# Mikrolysreklamen17.net
KiCad netlist of a schematic drawn in Altium Designer
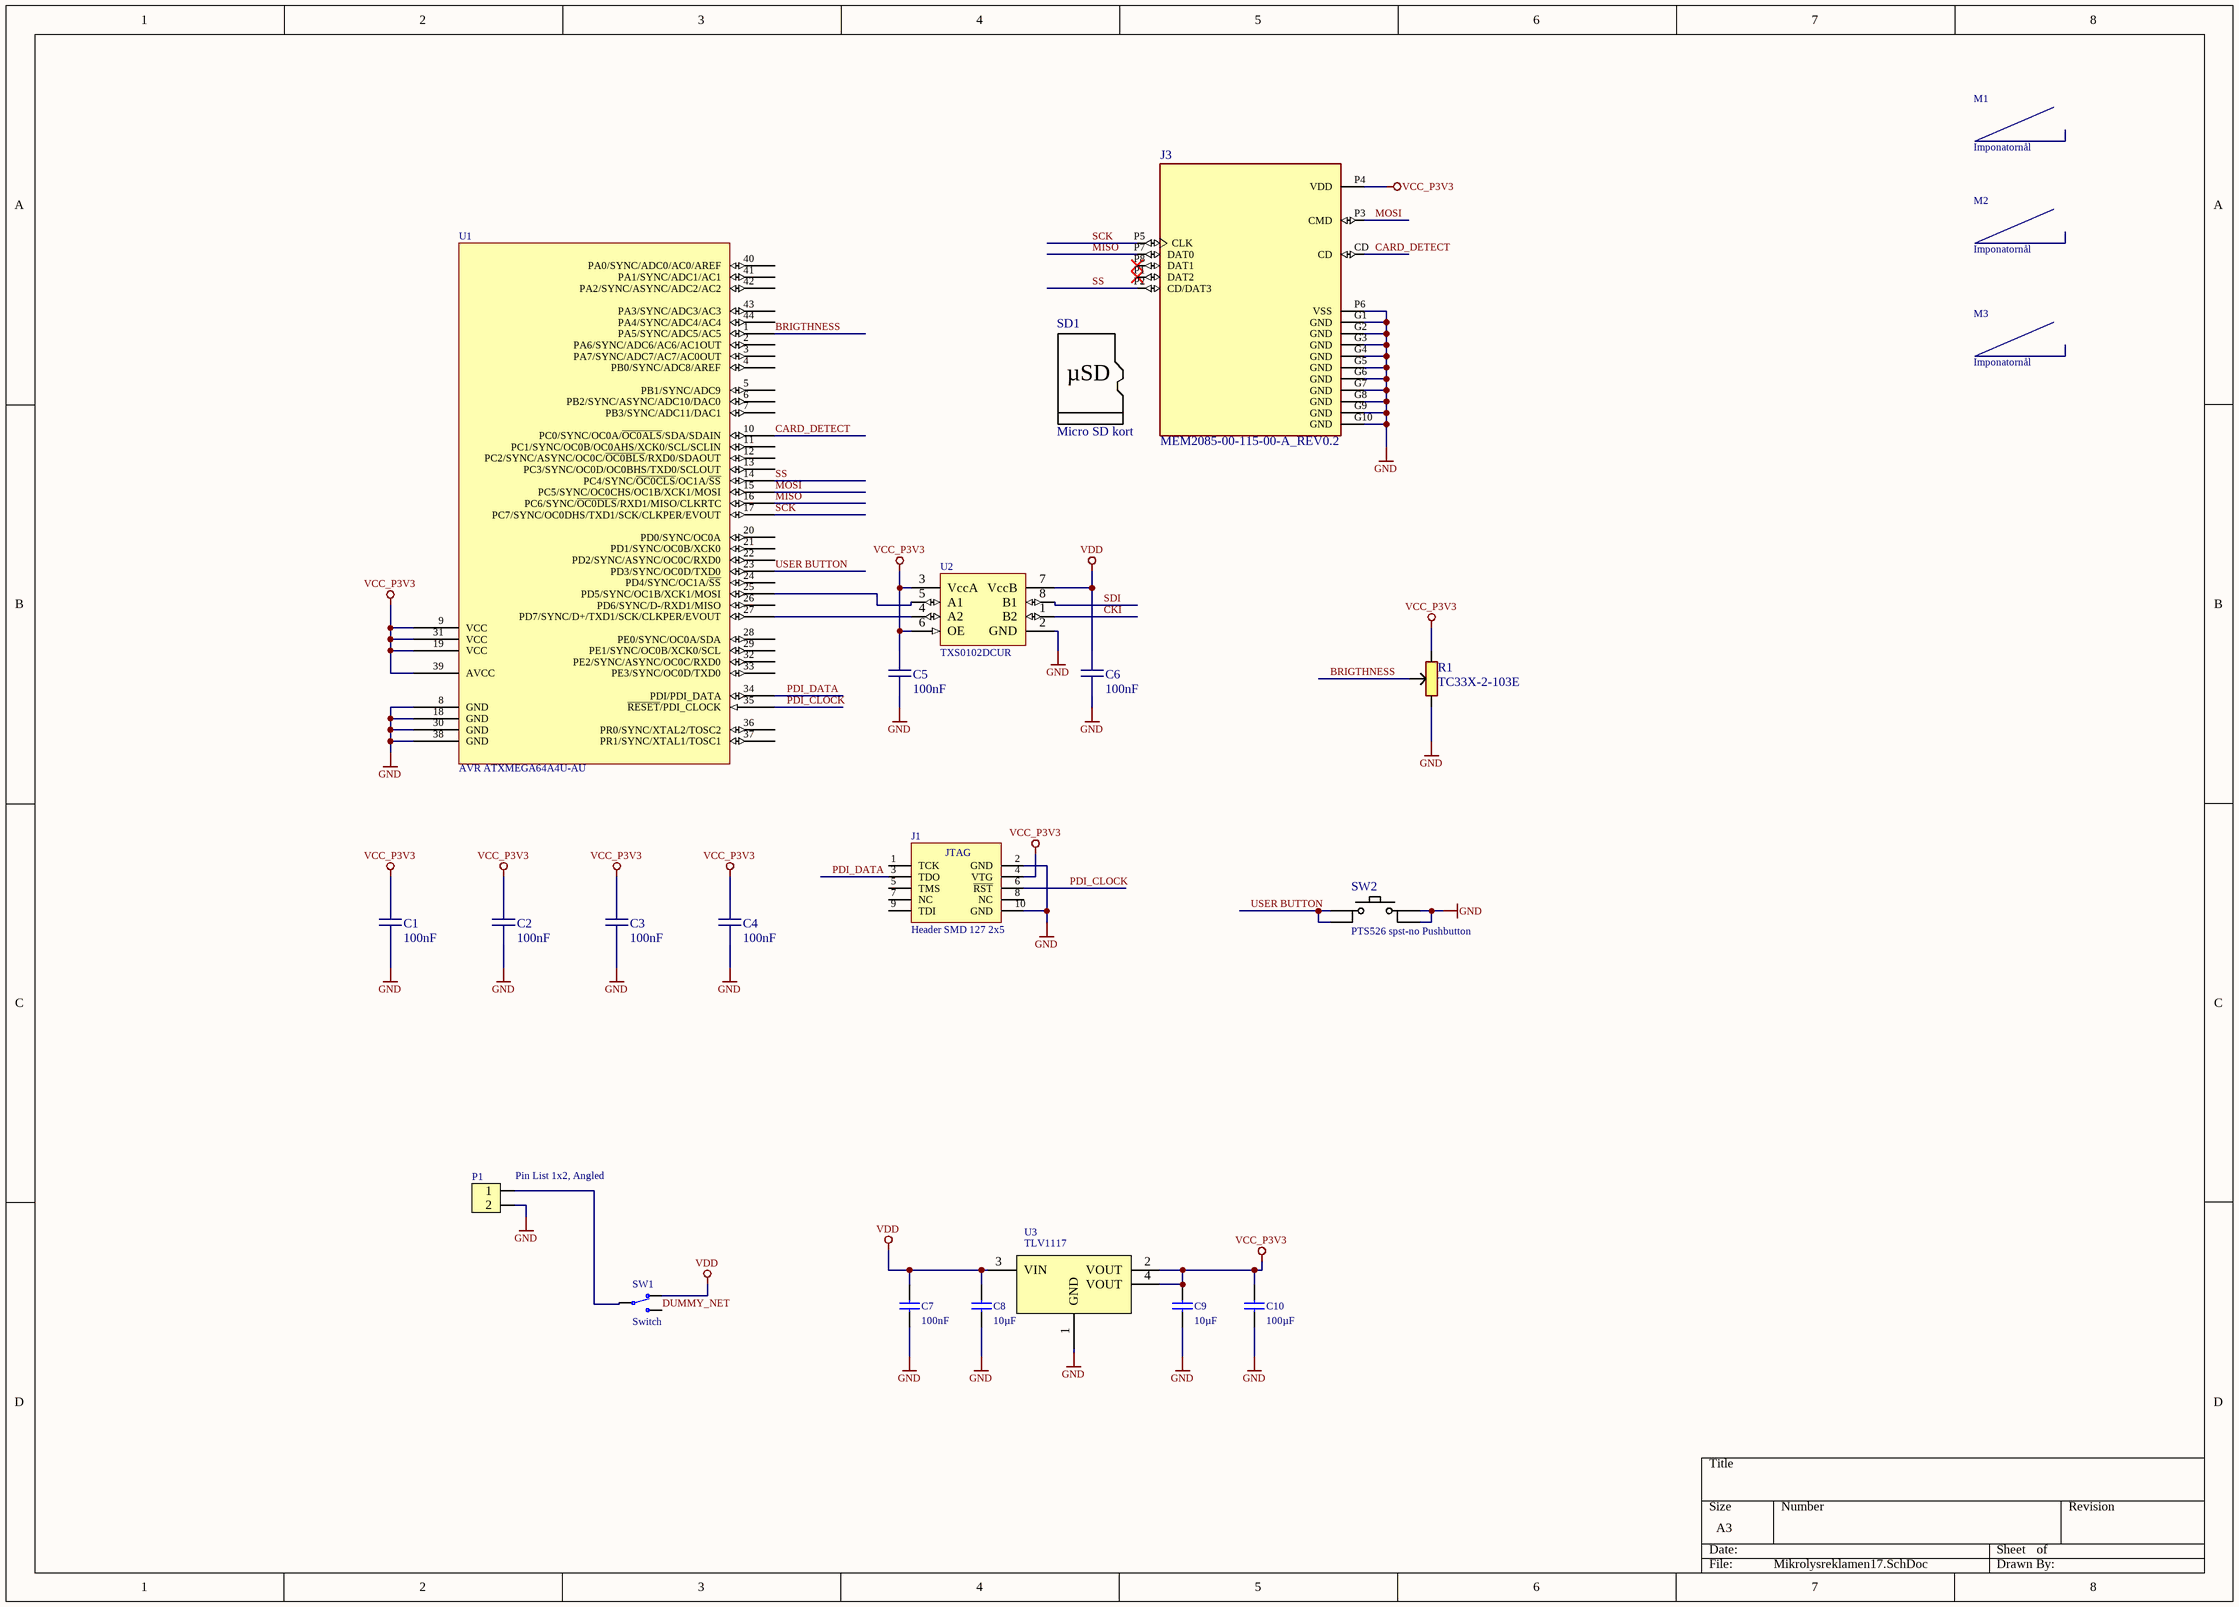
[diagram p0: Mikrolysreklamen17.SchDoc]

(export (version "E")
  (design (tool "Eeschema 10.0.6"))
  (components
    (comp (ref "C1")
      (value "100nF")
      (footprint "CAPC0603(1608)55_N")
      (libsource (lib "OVLib_64") (part "CAP"))
    )
    (comp (ref "C2")
      (value "100nF")
      (footprint "CAPC0603(1608)55_N")
      (libsource (lib "OVLib_64") (part "CAP"))
    )
    (comp (ref "C3")
      (value "100nF")
      (footprint "CAPC0603(1608)55_N")
      (libsource (lib "OVLib_64") (part "CAP"))
    )
    (comp (ref "C4")
      (value "100nF")
      (footprint "CAPC0603(1608)55_N")
      (libsource (lib "OVLib_64") (part "CAP"))
    )
    (comp (ref "C5")
      (value "100nF")
      (footprint "CAPC0603(1608)55_N")
      (libsource (lib "OVLib_64") (part "CAP"))
    )
    (comp (ref "C6")
      (value "100nF")
      (footprint "CAPC0603(1608)55_N")
      (libsource (lib "OVLib_64") (part "CAP"))
    )
    (comp (ref "C7")
      (value "100nF")
      (footprint "CAPC1005X04L")
      (description "Capacitor, X7R, ±10%")
      (fields (field (name "PART NUMBER") "C0402-100n") (field (name "PUBLISHER") "Nordic Semiconductor"))
      (libsource (lib "Nordic Passive DB") (part "CAP"))
    )
    (comp (ref "C8")
      (value "10µF")
      (footprint "CAPC1608X06L")
      (description "Capacitor, X5R, ±20%")
      (fields (field (name "PART NUMBER") "C0603-10µ") (field (name "PUBLISHER") "Nordic Semiconductor"))
      (libsource (lib "Nordic Passive DB") (part "CAP"))
    )
    (comp (ref "C9")
      (value "10µF")
      (footprint "CAPC1608X06L")
      (description "Capacitor, X5R, ±20%")
      (fields (field (name "PART NUMBER") "C0603-10µ") (field (name "PUBLISHER") "Nordic Semiconductor"))
      (libsource (lib "Nordic Passive DB") (part "CAP"))
    )
    (comp (ref "C10")
      (value "100µF")
      (footprint "CAPC2012X11L")
      (description "Chip Cap 0805")
      (fields (field (name "PART NUMBER") "C0805-TBD") (field (name "PUBLISHER") "Nordic Semiconductor"))
      (libsource (lib "Nordic Passive DB") (part "CAP"))
    )
    (comp (ref "J1")
      (value "Header SMD 127 2x5")
      (footprint "SMDHDRV10P127_2X5_615X330X560B")
      (description "1,27mm Pitch SMD Header")
      (libsource (lib "OVLib") (part "AVRJTAG"))
    )
    (comp (ref "J3")
      (value "MEM2085-00-115-00-A_REV0.2")
      (footprint "GCT_MEM2085-00-115-00-A_REV0.2")
      (description "MicroSD Push pull Memory Card Connector")
      (fields (field (name "MP") "MEM2085-00-115-00-A") (field (name "MF") "Global Connector Technology"))
      (libsource (lib "OVLib_64") (part "MEM2085-00-115-00-A_REV0.2"))
    )
    (comp (ref "M1")
      (value "Imponatornål")
      (footprint "Imponatornaal_liten")
      (description "nål til imponatorplate 20mm (Brooch back)")
      (libsource (lib "OVLib_64") (part "Imponatornaal"))
    )
    (comp (ref "M2")
      (value "Imponatornål")
      (footprint "Imponatornaal_liten")
      (description "nål til imponatorplate 20mm (Brooch back)")
      (libsource (lib "OVLib_64") (part "Imponatornaal"))
    )
    (comp (ref "M3")
      (value "Imponatornål")
      (footprint "Imponatornaal_liten")
      (description "nål til imponatorplate 20mm (Brooch back)")
      (libsource (lib "OVLib_64") (part "Imponatornaal"))
    )
    (comp (ref "P1")
      (value "Pin List 1x2, Angled")
      (footprint "LIST_ANG_1x2-SMD-2.54MM")
      (description "Pin List 1x2, 2.54mm (100mil), Right Angled, SMD")
      (fields
        (field (name "PART NUMBER") "Pin List Ang 1x2 SMD, 2.54mm")
        (field (name "MANUFACTURER") "W-CON")
        (field (name "PUBLISHER") "Nordic Semiconductor")
      )
      (libsource (lib "Nordic Passive DB") (part "CONN-2"))
    )
    (comp (ref "R1")
      (value "TC33X-2-103E")
      (footprint "TRIM_TC33X-2-103E")
      (libsource (lib "OVLib_64") (part "Potmeter"))
    )
    (comp (ref "SD1")
      (value "Micro SD kort")
      (footprint "microsdcard")
      (libsource (lib "OVLib_64") (part "microsdcard"))
    )
    (comp (ref "SW1")
      (value "Switch")
      (footprint "JS102011SAQN")
      (description "SMD slide Switch (ON-ON)")
      (fields
        (field (name "PART NUMBER") "JS102011SAQN")
        (field (name "MANUFACTURER") "C&K Components")
        (field (name "PUBLISHER") "Nordic Semiconductor")
      )
      (libsource (lib "Nordic Discrete DB") (part "SW-SPDT"))
    )
    (comp (ref "SW2")
      (value "PTS526 spst-no Pushbutton")
      (footprint "PTS526_SK15_SMTR2_LFS")
      (libsource (lib "OVLib_64") (part "Pushbutton"))
    )
    (comp (ref "U1")
      (value "AVR ATXMEGA64A4U-AU")
      (footprint "TQFP80P1200X1200X120-44N")
      (description "Mikrokontroller")
      (libsource (lib "OVLib") (part "ATXMEGA-A4U"))
    )
    (comp (ref "U2")
      (value "TXS0102DCUR")
      (footprint "TSSOP50P310X90-8N")
      (description "IC VOLT-LEVEL TRANSLATOR 8-US8")
      (fields
        (field (name "MANUFACTURER") "Texas Instruments")
        (field (name "PUBLISHER") "Nordic Semiconductor")
      )
      (libsource (lib "Nordic Active DB") (part "TXS0102DC"))
    )
    (comp (ref "U3")
      (value "TLV1117")
      (footprint "SOT230P700X180-4N")
      (description "REG LDO 3.3V 0.8A SOT223")
      (fields
        (field (name "PART NUMBER") "TLV1117-33CDCYR")
        (field (name "MANUFACTURER") "Texas Instruments")
        (field (name "PUBLISHER") "Nordic Semiconductor")
      )
      (libsource (lib "Nordic Active DB") (part "LD1117_fixed"))
    )
  )
  (nets
    (net (code "1") (name "/BRIGTHNESS") (class "Default")
      (node (ref "R1") (pin "2") (pinfunction "2_2") (pintype "passive"))
      (node (ref "U1") (pin "1") (pinfunction "PA5/SYNC/ADC5/AC5_1") (pintype "bidirectional"))
    )
    (net (code "2") (name "/CARD_DETECT") (class "Default")
      (node (ref "J3") (pin "CD") (pinfunction "CD_CD") (pintype "bidirectional"))
      (node (ref "U1") (pin "10") (pinfunction "PC0/SYNC/OC0A/~{OC0ALS}/SDA/SDAIN_10") (pintype "bidirectional"))
    )
    (net (code "3") (name "/CKI") (class "Default")
      (node (ref "U2") (pin "1") (pinfunction "B2_1") (pintype "bidirectional"))
    )
    (net (code "4") (name "/DUMMY_NET") (class "Default")
      (node (ref "SW1") (pin "3") (pinfunction "N.O_3") (pintype "passive"))
    )
    (net (code "5") (name "/MISO") (class "Default")
      (node (ref "J3") (pin "P7") (pinfunction "DAT0_P7") (pintype "bidirectional"))
      (node (ref "U1") (pin "16") (pinfunction "PC6/SYNC/~{OC0DLS}/RXD1/MISO/CLKRTC_16") (pintype "bidirectional"))
    )
    (net (code "6") (name "/MOSI") (class "Default")
      (node (ref "J3") (pin "P3") (pinfunction "CMD_P3") (pintype "bidirectional"))
      (node (ref "U1") (pin "15") (pinfunction "PC5/SYNC/OC0CHS/OC1B/XCK1/MOSI_15") (pintype "bidirectional"))
    )
    (net (code "7") (name "/PDI_CLOCK") (class "Default")
      (node (ref "J1") (pin "6") (pinfunction "~{RST}_6") (pintype "passive"))
      (node (ref "U1") (pin "35") (pinfunction "~{RESET}/PDI_CLOCK_35") (pintype "input"))
    )
    (net (code "8") (name "/PDI_DATA") (class "Default")
      (node (ref "J1") (pin "3") (pinfunction "TDO_3") (pintype "passive"))
      (node (ref "U1") (pin "34") (pinfunction "PDI/PDI_DATA_34") (pintype "bidirectional"))
    )
    (net (code "9") (name "/SCK") (class "Default")
      (node (ref "J3") (pin "P5") (pinfunction "CLK_P5") (pintype "bidirectional"))
      (node (ref "U1") (pin "17") (pinfunction "PC7/SYNC/OC0DHS/TXD1/SCK/CLKPER/EVOUT_17") (pintype "bidirectional"))
    )
    (net (code "10") (name "/SDI") (class "Default")
      (node (ref "U2") (pin "8") (pinfunction "B1_8") (pintype "bidirectional"))
    )
    (net (code "11") (name "/SS") (class "Default")
      (node (ref "J3") (pin "P2") (pinfunction "CD/DAT3_P2") (pintype "bidirectional"))
      (node (ref "U1") (pin "14") (pinfunction "PC4/SYNC/~{OC0CLS}/OC1A/~{SS}_14") (pintype "bidirectional"))
    )
    (net (code "12") (name "/USER BUTTON") (class "Default")
      (node (ref "SW2") (pin "1") (pinfunction "1_1") (pintype "passive"))
      (node (ref "SW2") (pin "2") (pinfunction "2_2") (pintype "passive"))
      (node (ref "U1") (pin "23") (pinfunction "PD3/SYNC/OC0D/TXD0_23") (pintype "bidirectional"))
    )
    (net (code "13") (name "GND") (class "Default")
      (node (ref "C1") (pin "1") (pinfunction "1_1") (pintype "passive"))
      (node (ref "C10") (pin "1") (pinfunction "1_1") (pintype "passive"))
      (node (ref "C2") (pin "1") (pinfunction "1_1") (pintype "passive"))
      (node (ref "C3") (pin "1") (pinfunction "1_1") (pintype "passive"))
      (node (ref "C4") (pin "1") (pinfunction "1_1") (pintype "passive"))
      (node (ref "C5") (pin "1") (pinfunction "1_1") (pintype "passive"))
      (node (ref "C6") (pin "1") (pinfunction "1_1") (pintype "passive"))
      (node (ref "C7") (pin "1") (pinfunction "1_1") (pintype "passive"))
      (node (ref "C8") (pin "1") (pinfunction "1_1") (pintype "passive"))
      (node (ref "C9") (pin "1") (pinfunction "1_1") (pintype "passive"))
      (node (ref "J1") (pin "10") (pinfunction "GND_10") (pintype "passive"))
      (node (ref "J1") (pin "2") (pinfunction "GND_2") (pintype "passive"))
      (node (ref "J3") (pin "G1") (pinfunction "GND_G1") (pintype "power_in"))
      (node (ref "J3") (pin "G10") (pinfunction "GND_G10") (pintype "power_in"))
      (node (ref "J3") (pin "G2") (pinfunction "GND_G2") (pintype "power_in"))
      (node (ref "J3") (pin "G3") (pinfunction "GND_G3") (pintype "power_in"))
      (node (ref "J3") (pin "G4") (pinfunction "GND_G4") (pintype "power_in"))
      (node (ref "J3") (pin "G5") (pinfunction "GND_G5") (pintype "power_in"))
      (node (ref "J3") (pin "G6") (pinfunction "GND_G6") (pintype "power_in"))
      (node (ref "J3") (pin "G7") (pinfunction "GND_G7") (pintype "power_in"))
      (node (ref "J3") (pin "G8") (pinfunction "GND_G8") (pintype "power_in"))
      (node (ref "J3") (pin "G9") (pinfunction "GND_G9") (pintype "power_in"))
      (node (ref "J3") (pin "P6") (pinfunction "VSS_P6") (pintype "power_in"))
      (node (ref "P1") (pin "2") (pinfunction "2_2") (pintype "passive"))
      (node (ref "R1") (pin "1") (pinfunction "1_1") (pintype "passive"))
      (node (ref "SW2") (pin "3") (pinfunction "3_3") (pintype "passive"))
      (node (ref "SW2") (pin "4") (pinfunction "4_4") (pintype "passive"))
      (node (ref "U1") (pin "18") (pinfunction "GND_18") (pintype "power_in"))
      (node (ref "U1") (pin "30") (pinfunction "GND_30") (pintype "power_in"))
      (node (ref "U1") (pin "38") (pinfunction "GND_38") (pintype "power_in"))
      (node (ref "U1") (pin "8") (pinfunction "GND_8") (pintype "power_in"))
      (node (ref "U2") (pin "2") (pinfunction "GND_2") (pintype "power_in"))
      (node (ref "U3") (pin "1") (pinfunction "GND_1") (pintype "power_in"))
    )
    (net (code "14") (name "Net-(SW1-COM)") (class "Default")
      (node (ref "P1") (pin "1") (pinfunction "1_1") (pintype "passive"))
      (node (ref "SW1") (pin "2") (pinfunction "COM_2") (pintype "passive"))
    )
    (net (code "15") (name "Net-(U1-PD5{slash}SYNC{slash}OC1B{slash}XCK1{slash}MOSI)") (class "Default")
      (node (ref "U1") (pin "25") (pinfunction "PD5/SYNC/OC1B/XCK1/MOSI_25") (pintype "bidirectional"))
      (node (ref "U2") (pin "5") (pinfunction "A1_5") (pintype "bidirectional"))
    )
    (net (code "16") (name "Net-(U1-PD7{slash}SYNC{slash}D+{slash}TXD1{slash}SCK{slash}CLKPER{slash}EVOUT)") (class "Default")
      (node (ref "U1") (pin "27") (pinfunction "PD7/SYNC/D+/TXD1/SCK/CLKPER/EVOUT_27") (pintype "bidirectional"))
      (node (ref "U2") (pin "4") (pinfunction "A2_4") (pintype "bidirectional"))
    )
    (net (code "17") (name "VCC_P3V3") (class "Default")
      (node (ref "C1") (pin "2") (pinfunction "2_2") (pintype "passive"))
      (node (ref "C10") (pin "2") (pinfunction "2_2") (pintype "passive"))
      (node (ref "C2") (pin "2") (pinfunction "2_2") (pintype "passive"))
      (node (ref "C3") (pin "2") (pinfunction "2_2") (pintype "passive"))
      (node (ref "C4") (pin "2") (pinfunction "2_2") (pintype "passive"))
      (node (ref "C5") (pin "2") (pinfunction "2_2") (pintype "passive"))
      (node (ref "C9") (pin "2") (pinfunction "2_2") (pintype "passive"))
      (node (ref "J1") (pin "4") (pinfunction "VTG_4") (pintype "passive"))
      (node (ref "J3") (pin "P4") (pinfunction "VDD_P4") (pintype "power_in"))
      (node (ref "R1") (pin "3") (pinfunction "3_3") (pintype "passive"))
      (node (ref "U1") (pin "19") (pinfunction "VCC_19") (pintype "power_in"))
      (node (ref "U1") (pin "31") (pinfunction "VCC_31") (pintype "power_in"))
      (node (ref "U1") (pin "39") (pinfunction "AVCC_39") (pintype "power_in"))
      (node (ref "U1") (pin "9") (pinfunction "VCC_9") (pintype "power_in"))
      (node (ref "U2") (pin "3") (pinfunction "VccA_3") (pintype "power_in"))
      (node (ref "U2") (pin "6") (pinfunction "OE_6") (pintype "input"))
      (node (ref "U3") (pin "2") (pinfunction "VOUT_2") (pintype "power_in"))
      (node (ref "U3") (pin "4") (pinfunction "VOUT_4") (pintype "power_in"))
    )
    (net (code "18") (name "VDD") (class "Default")
      (node (ref "C6") (pin "2") (pinfunction "2_2") (pintype "passive"))
      (node (ref "C7") (pin "2") (pinfunction "2_2") (pintype "passive"))
      (node (ref "C8") (pin "2") (pinfunction "2_2") (pintype "passive"))
      (node (ref "SW1") (pin "1") (pinfunction "N.C_1") (pintype "passive"))
      (node (ref "U2") (pin "7") (pinfunction "VccB_7") (pintype "power_in"))
      (node (ref "U3") (pin "3") (pinfunction "VIN_3") (pintype "power_in"))
    )
    (net (code "19") (name "unconnected-(J1-NC-Pad7)") (class "Default")
      (node (ref "J1") (pin "7") (pinfunction "NC_7") (pintype "passive"))
    )
    (net (code "20") (name "unconnected-(J1-NC-Pad8)") (class "Default")
      (node (ref "J1") (pin "8") (pinfunction "NC_8") (pintype "passive"))
    )
    (net (code "21") (name "unconnected-(J1-TCK-Pad1)") (class "Default")
      (node (ref "J1") (pin "1") (pinfunction "TCK_1") (pintype "passive"))
    )
    (net (code "22") (name "unconnected-(J1-TDI-Pad9)") (class "Default")
      (node (ref "J1") (pin "9") (pinfunction "TDI_9") (pintype "passive"))
    )
    (net (code "23") (name "unconnected-(J1-TMS-Pad5)") (class "Default")
      (node (ref "J1") (pin "5") (pinfunction "TMS_5") (pintype "passive"))
    )
    (net (code "24") (name "unconnected-(J3-DAT1-PadP8)") (class "Default")
      (node (ref "J3") (pin "P8") (pinfunction "DAT1_P8") (pintype "bidirectional+no_connect"))
    )
    (net (code "25") (name "unconnected-(J3-DAT2-PadP1)") (class "Default")
      (node (ref "J3") (pin "P1") (pinfunction "DAT2_P1") (pintype "bidirectional+no_connect"))
    )
    (net (code "26") (name "unconnected-(U1-PA0{slash}SYNC{slash}ADC0{slash}AC0{slash}AREF-Pad40)") (class "Default")
      (node (ref "U1") (pin "40") (pinfunction "PA0/SYNC/ADC0/AC0/AREF_40") (pintype "bidirectional"))
    )
    (net (code "27") (name "unconnected-(U1-PA1{slash}SYNC{slash}ADC1{slash}AC1-Pad41)") (class "Default")
      (node (ref "U1") (pin "41") (pinfunction "PA1/SYNC/ADC1/AC1_41") (pintype "bidirectional"))
    )
    (net (code "28") (name "unconnected-(U1-PA2{slash}SYNC{slash}ASYNC{slash}ADC2{slash}AC2-Pad42)") (class "Default")
      (node (ref "U1") (pin "42") (pinfunction "PA2/SYNC/ASYNC/ADC2/AC2_42") (pintype "bidirectional"))
    )
    (net (code "29") (name "unconnected-(U1-PA3{slash}SYNC{slash}ADC3{slash}AC3-Pad43)") (class "Default")
      (node (ref "U1") (pin "43") (pinfunction "PA3/SYNC/ADC3/AC3_43") (pintype "bidirectional"))
    )
    (net (code "30") (name "unconnected-(U1-PA4{slash}SYNC{slash}ADC4{slash}AC4-Pad44)") (class "Default")
      (node (ref "U1") (pin "44") (pinfunction "PA4/SYNC/ADC4/AC4_44") (pintype "bidirectional"))
    )
    (net (code "31") (name "unconnected-(U1-PA6{slash}SYNC{slash}ADC6{slash}AC6{slash}AC1OUT-Pad2)") (class "Default")
      (node (ref "U1") (pin "2") (pinfunction "PA6/SYNC/ADC6/AC6/AC1OUT_2") (pintype "bidirectional"))
    )
    (net (code "32") (name "unconnected-(U1-PA7{slash}SYNC{slash}ADC7{slash}AC7{slash}AC0OUT-Pad3)") (class "Default")
      (node (ref "U1") (pin "3") (pinfunction "PA7/SYNC/ADC7/AC7/AC0OUT_3") (pintype "bidirectional"))
    )
    (net (code "33") (name "unconnected-(U1-PB0{slash}SYNC{slash}ADC8{slash}AREF-Pad4)") (class "Default")
      (node (ref "U1") (pin "4") (pinfunction "PB0/SYNC/ADC8/AREF_4") (pintype "bidirectional"))
    )
    (net (code "34") (name "unconnected-(U1-PB1{slash}SYNC{slash}ADC9-Pad5)") (class "Default")
      (node (ref "U1") (pin "5") (pinfunction "PB1/SYNC/ADC9_5") (pintype "bidirectional"))
    )
    (net (code "35") (name "unconnected-(U1-PB2{slash}SYNC{slash}ASYNC{slash}ADC10{slash}DAC0-Pad6)") (class "Default")
      (node (ref "U1") (pin "6") (pinfunction "PB2/SYNC/ASYNC/ADC10/DAC0_6") (pintype "bidirectional"))
    )
    (net (code "36") (name "unconnected-(U1-PB3{slash}SYNC{slash}ADC11{slash}DAC1-Pad7)") (class "Default")
      (node (ref "U1") (pin "7") (pinfunction "PB3/SYNC/ADC11/DAC1_7") (pintype "bidirectional"))
    )
    (net (code "37") (name "unconnected-(U1-PC1{slash}SYNC{slash}OC0B{slash}OC0AHS{slash}XCK0{slash}SCL{slash}SCLIN-Pad11)") (class "Default")
      (node (ref "U1") (pin "11") (pinfunction "PC1/SYNC/OC0B/OC0AHS/XCK0/SCL/SCLIN_11") (pintype "bidirectional"))
    )
    (net (code "38") (name "unconnected-(U1-PC2{slash}SYNC{slash}ASYNC{slash}OC0C{slash}~{OC0BLS}{slash}RXD0{slash}SDAOUT-Pad12)") (class "Default")
      (node (ref "U1") (pin "12") (pinfunction "PC2/SYNC/ASYNC/OC0C/~{OC0BLS}/RXD0/SDAOUT_12") (pintype "bidirectional"))
    )
    (net (code "39") (name "unconnected-(U1-PC3{slash}SYNC{slash}OC0D{slash}OC0BHS{slash}TXD0{slash}SCLOUT-Pad13)") (class "Default")
      (node (ref "U1") (pin "13") (pinfunction "PC3/SYNC/OC0D/OC0BHS/TXD0/SCLOUT_13") (pintype "bidirectional"))
    )
    (net (code "40") (name "unconnected-(U1-PD0{slash}SYNC{slash}OC0A-Pad20)") (class "Default")
      (node (ref "U1") (pin "20") (pinfunction "PD0/SYNC/OC0A_20") (pintype "bidirectional"))
    )
    (net (code "41") (name "unconnected-(U1-PD1{slash}SYNC{slash}OC0B{slash}XCK0-Pad21)") (class "Default")
      (node (ref "U1") (pin "21") (pinfunction "PD1/SYNC/OC0B/XCK0_21") (pintype "bidirectional"))
    )
    (net (code "42") (name "unconnected-(U1-PD2{slash}SYNC{slash}ASYNC{slash}OC0C{slash}RXD0-Pad22)") (class "Default")
      (node (ref "U1") (pin "22") (pinfunction "PD2/SYNC/ASYNC/OC0C/RXD0_22") (pintype "bidirectional"))
    )
    (net (code "43") (name "unconnected-(U1-PD4{slash}SYNC{slash}OC1A{slash}~{SS}-Pad24)") (class "Default")
      (node (ref "U1") (pin "24") (pinfunction "PD4/SYNC/OC1A/~{SS}_24") (pintype "bidirectional"))
    )
    (net (code "44") (name "unconnected-(U1-PD6{slash}SYNC{slash}D-{slash}RXD1{slash}MISO-Pad26)") (class "Default")
      (node (ref "U1") (pin "26") (pinfunction "PD6/SYNC/D-/RXD1/MISO_26") (pintype "bidirectional"))
    )
    (net (code "45") (name "unconnected-(U1-PE0{slash}SYNC{slash}OC0A{slash}SDA-Pad28)") (class "Default")
      (node (ref "U1") (pin "28") (pinfunction "PE0/SYNC/OC0A/SDA_28") (pintype "bidirectional"))
    )
    (net (code "46") (name "unconnected-(U1-PE1{slash}SYNC{slash}OC0B{slash}XCK0{slash}SCL-Pad29)") (class "Default")
      (node (ref "U1") (pin "29") (pinfunction "PE1/SYNC/OC0B/XCK0/SCL_29") (pintype "bidirectional"))
    )
    (net (code "47") (name "unconnected-(U1-PE2{slash}SYNC{slash}ASYNC{slash}OC0C{slash}RXD0-Pad32)") (class "Default")
      (node (ref "U1") (pin "32") (pinfunction "PE2/SYNC/ASYNC/OC0C/RXD0_32") (pintype "bidirectional"))
    )
    (net (code "48") (name "unconnected-(U1-PE3{slash}SYNC{slash}OC0D{slash}TXD0-Pad33)") (class "Default")
      (node (ref "U1") (pin "33") (pinfunction "PE3/SYNC/OC0D/TXD0_33") (pintype "bidirectional"))
    )
    (net (code "49") (name "unconnected-(U1-PR0{slash}SYNC{slash}XTAL2{slash}TOSC2-Pad36)") (class "Default")
      (node (ref "U1") (pin "36") (pinfunction "PR0/SYNC/XTAL2/TOSC2_36") (pintype "bidirectional"))
    )
    (net (code "50") (name "unconnected-(U1-PR1{slash}SYNC{slash}XTAL1{slash}TOSC1-Pad37)") (class "Default")
      (node (ref "U1") (pin "37") (pinfunction "PR1/SYNC/XTAL1/TOSC1_37") (pintype "bidirectional"))
    )
  )
)
